# design.net
KiCad netlist of a schematic drawn in EasyEDA Pro
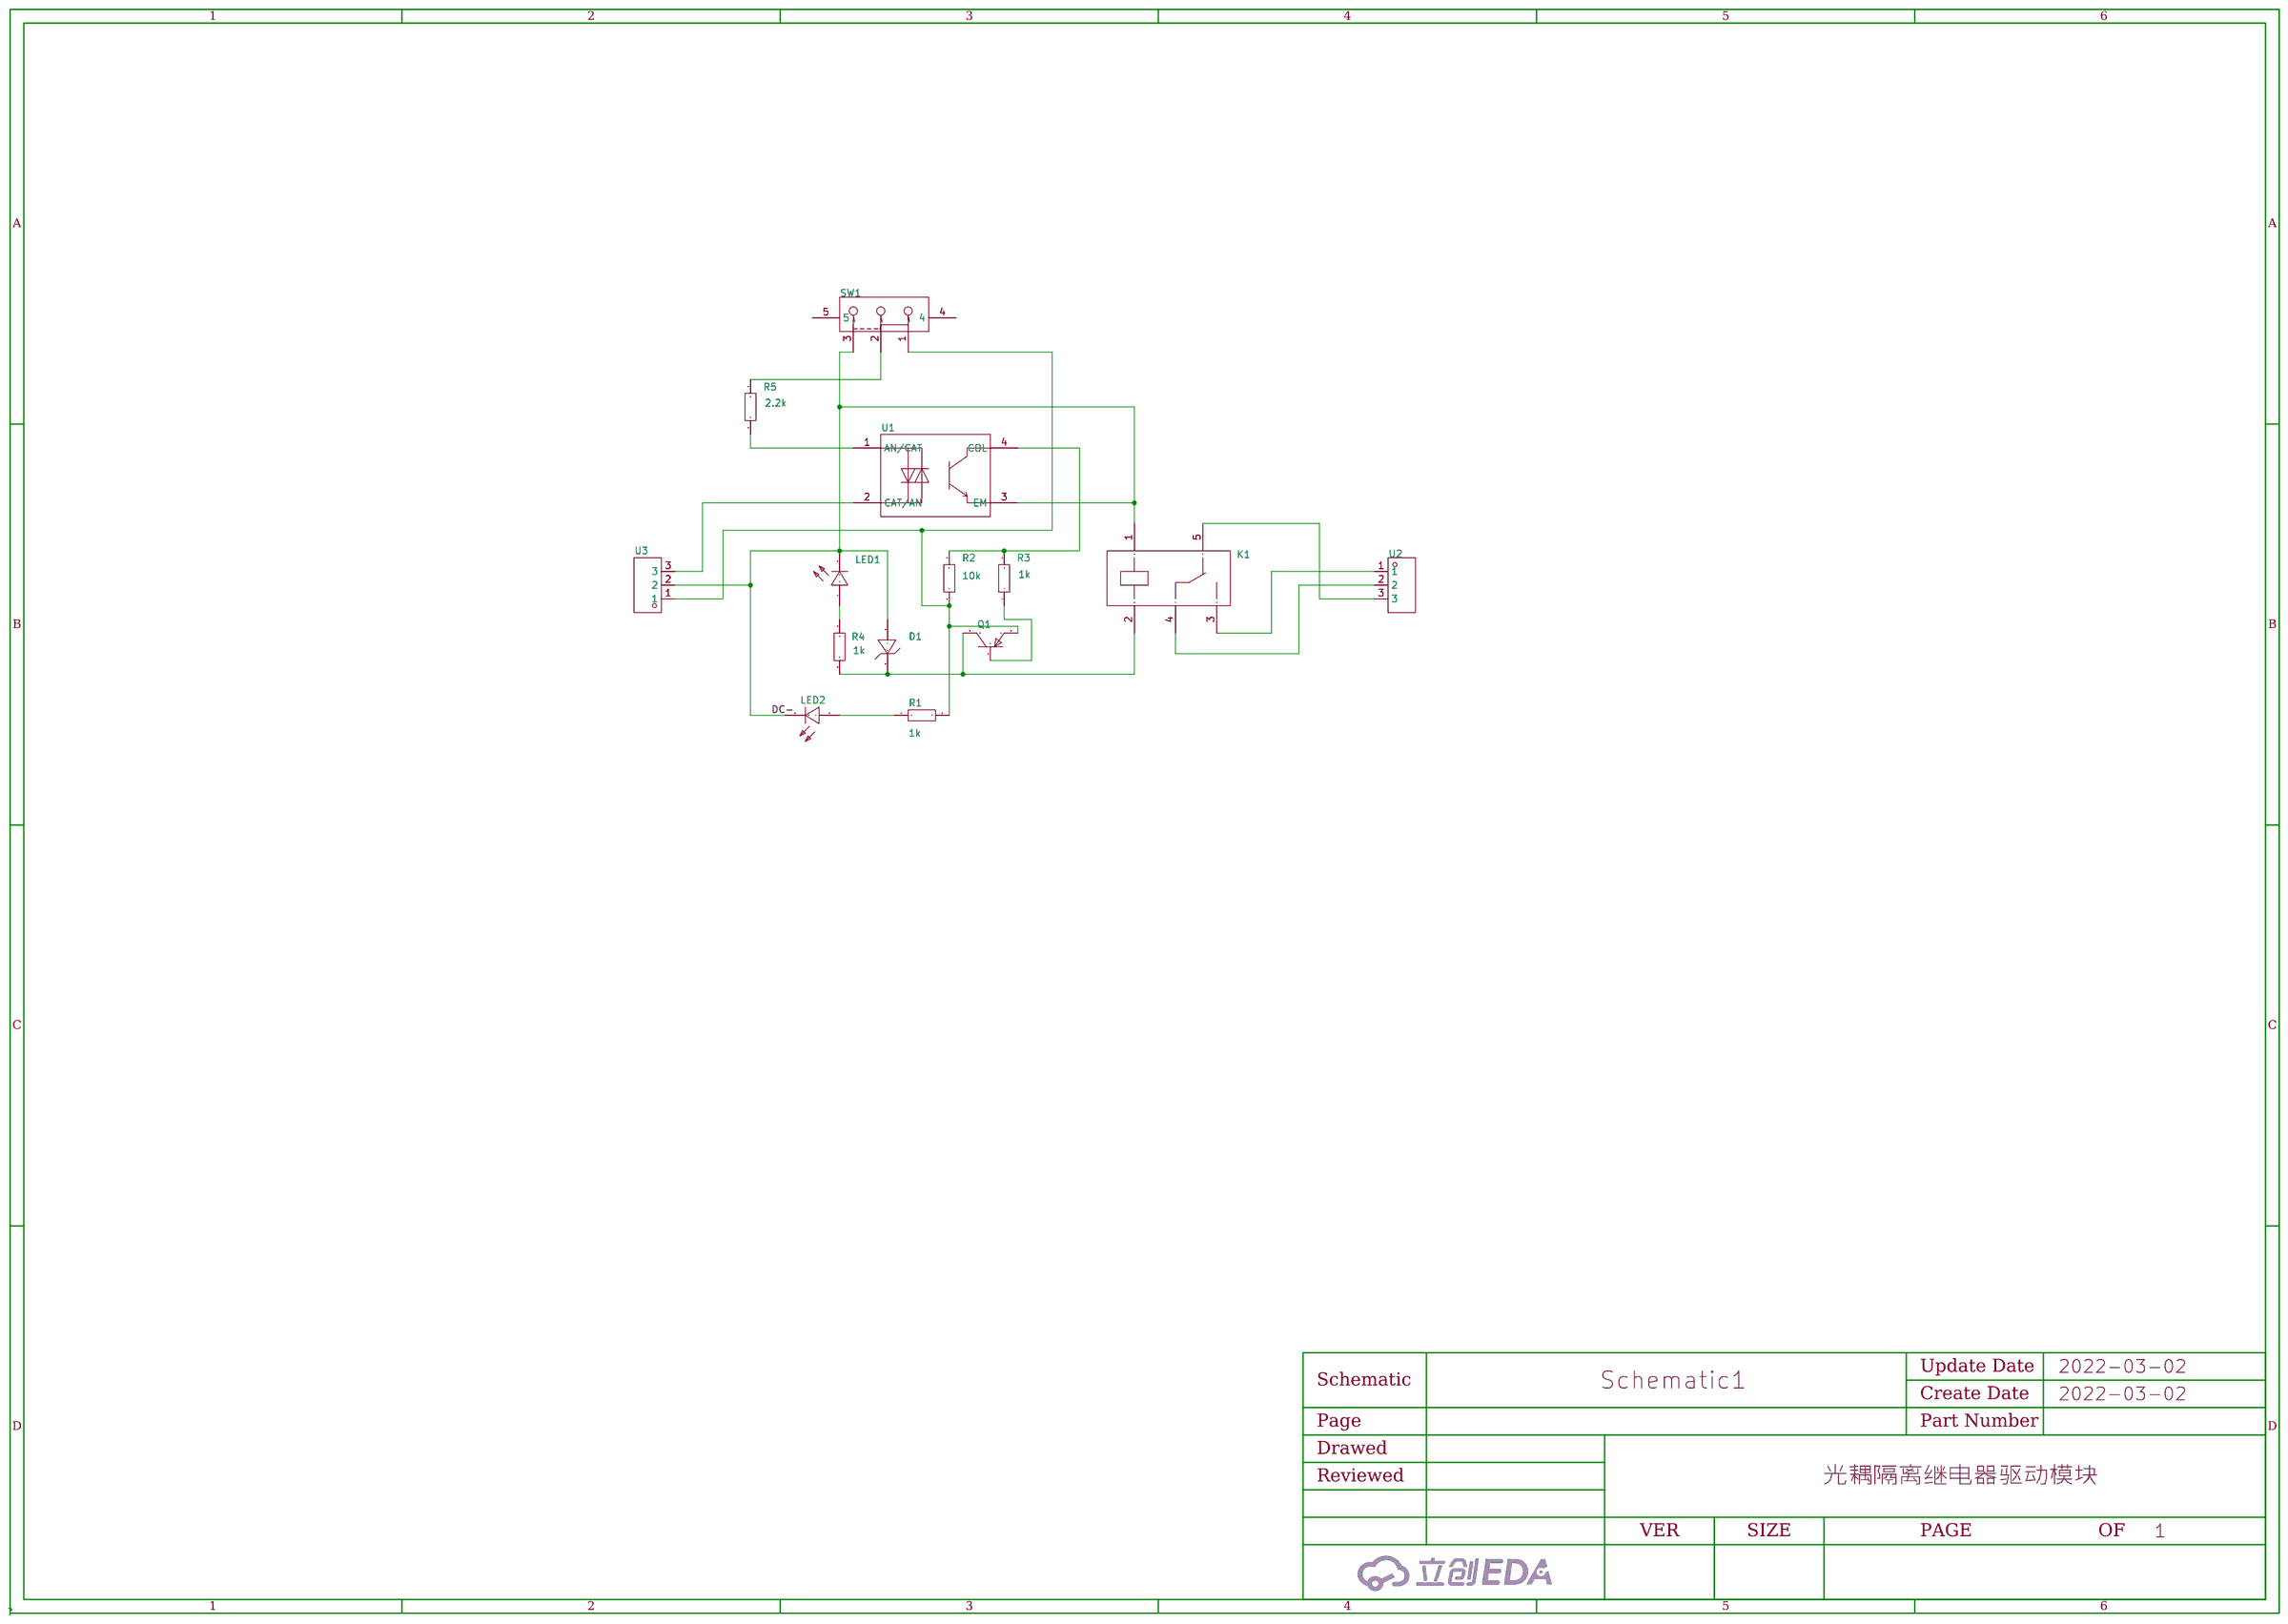
[diagram p0: schematic sheet]

(export (version "E")
  (design (tool "Eeschema 10.0.6"))
  (components
    (comp (ref "D1")
      (value "~")
      (footprint "easyedapro:LL-34_L3.5-W1.5-RD")
      (description "二极管配置:独立式;稳压值(标称值):-;稳压值(范围):4.94V~5.2V;精度:-;功率:500mW;反向电流(Ir):5A@1.5V;阻抗(Zzt):20;")
      (fields
        (field (name "Manufacturer Part") "GLZ5.1B_R1_10001")
        (field (name "Manufacturer") "PANJIT(强茂)")
      )
      (libsource (lib "easyedapro") (part "GLZ5.1B_R1_10001"))
    )
    (comp (ref "K1")
      (value "~")
      (footprint "easyedapro:RELAY-TH_HF3FF-XX-1ZXX-XXX")
      (description "继电器类型:General Purpose;线圈类型:Non Latching;线圈电压:5VDC;触点形式:SPDT;触点的额定电流:10A;")
      (fields
        (field (name "Manufacturer Part") "JQC-3FF/005-1ZS(551)")
        (field (name "Manufacturer") "HF(宏发)")
      )
      (libsource (lib "easyedapro") (part "JQC-3FF/05-1ZS(551)"))
    )
    (comp (ref "LED1")
      (value "~")
      (footprint "easyedapro:LED0603-R-RD")
      (fields
        (field (name "Manufacturer Part") "19-217/GHC-YR1S2/3T")
        (field (name "Manufacturer") "EVERLIGHT(台湾亿光)")
      )
      (libsource (lib "easyedapro") (part "19-217/GHC-YR1S2/3T"))
    )
    (comp (ref "LED2")
      (value "~")
      (footprint "easyedapro:LED0603-R-RD")
      (fields
        (field (name "Manufacturer Part") "19-217/GHC-YR1S2/3T")
        (field (name "Manufacturer") "EVERLIGHT(台湾亿光)")
      )
      (libsource (lib "easyedapro") (part "19-217/GHC-YR1S2/3T"))
    )
    (comp (ref "Q1")
      (value "~")
      (footprint "easyedapro:SOT-23-3_L2.9-W1.3-P1.90-LS2.4-BR")
      (description "晶体管类型:PNP;集射极击穿电压(Vceo):25V;集电极电流(Ic):500mA;功率(Pd):300mW;")
      (fields (field (name "Manufacturer Part") "S8550 2TY") (field (name "Manufacturer") "CJ（江苏长电/长晶）"))
      (libsource (lib "easyedapro") (part "S8550_C2147"))
    )
    (comp (ref "R1")
      (value "1k")
      (footprint "easyedapro:R0603")
      (description "电阻类型:薄膜电阻;阻值:10k;精度:±0.1%;功率:100mW;温度系数:±25ppm/;最大工作电压:75V;工作温度范围:-55~+155;")
      (fields
        (field (name "Manufacturer Part") "TR0603B10K0P0525Z")
        (field (name "Manufacturer") "EVER OHMS(天二科技)")
      )
      (libsource (lib "easyedapro") (part "TR0603B10KP05250.1W"))
    )
    (comp (ref "R2")
      (value "10k")
      (footprint "easyedapro:R0603")
      (description "电阻类型:薄膜电阻;阻值:10k;精度:±0.1%;功率:100mW;温度系数:±25ppm/;最大工作电压:75V;工作温度范围:-55~+155;")
      (fields
        (field (name "Manufacturer Part") "TR0603B10K0P0525Z")
        (field (name "Manufacturer") "EVER OHMS(天二科技)")
      )
      (libsource (lib "easyedapro") (part "TR0603B10KP05250.1W"))
    )
    (comp (ref "R3")
      (value "1k")
      (footprint "easyedapro:R0603")
      (description "电阻类型:薄膜电阻;阻值:10k;精度:±0.1%;功率:100mW;温度系数:±25ppm/;最大工作电压:75V;工作温度范围:-55~+155;")
      (fields
        (field (name "Manufacturer Part") "TR0603B10K0P0525Z")
        (field (name "Manufacturer") "EVER OHMS(天二科技)")
      )
      (libsource (lib "easyedapro") (part "TR0603B10KP05250.1W"))
    )
    (comp (ref "R4")
      (value "1k")
      (footprint "easyedapro:R0603")
      (description "电阻类型:薄膜电阻;阻值:10k;精度:±0.1%;功率:100mW;温度系数:±25ppm/;最大工作电压:75V;工作温度范围:-55~+155;")
      (fields
        (field (name "Manufacturer Part") "TR0603B10K0P0525Z")
        (field (name "Manufacturer") "EVER OHMS(天二科技)")
      )
      (libsource (lib "easyedapro") (part "TR0603B10KP05250.1W"))
    )
    (comp (ref "R5")
      (value "2.2k")
      (footprint "easyedapro:R0603")
      (description "电阻类型:薄膜电阻;阻值:10k;精度:±0.1%;功率:100mW;温度系数:±25ppm/;最大工作电压:75V;工作温度范围:-55~+155;")
      (fields
        (field (name "Manufacturer Part") "TR0603B10K0P0525Z")
        (field (name "Manufacturer") "EVER OHMS(天二科技)")
      )
      (libsource (lib "easyedapro") (part "TR0603B10KP05250.1W"))
    )
    (comp (ref "SW1")
      (value "~")
      (footprint "easyedapro:SW-TH_SK-12D02VG3")
      (fields (field (name "Manufacturer Part") "SK-12D02VG3") (field (name "Manufacturer") "SOFNG(硕方)"))
      (libsource (lib "easyedapro") (part "SK-12D02"))
    )
    (comp (ref "U1")
      (value "~")
      (footprint "easyedapro:SOP-4_L3.9-W4.4-P2.54-LS7.0-TL")
      (description "产品类型:晶体管输出;输入类型:AC, DC;通道数目:1;隔离电压:3750Vrms;")
      (fields (field (name "Manufacturer Part") "LTV-354T-A") (field (name "Manufacturer") "LITEON(台湾光宝)"))
      (libsource (lib "easyedapro") (part "LTV-354T-A"))
    )
    (comp (ref "U2")
      (value "~")
      (footprint "easyedapro:CONN-TH_3P-P5.00_KF301-5.0-3P")
      (description "间距:5mm;排数:1;每排PIN数:3;安装方式:直针;额定电流:17A;额定电压:250V;线规 - AWG:14~22;线规 - mm?:1.5;工作温度范围:-30~+120;颜色:蓝色;")
      (fields (field (name "Manufacturer Part") "KF301-5.0-3P") (field (name "Manufacturer") "KEFA(科发)"))
      (libsource (lib "easyedapro") (part "KF301-5.0-3P"))
    )
    (comp (ref "U3")
      (value "~")
      (footprint "easyedapro:CONN-TH_3P-P5.00_KF301-5.0-3P")
      (description "间距:5mm;排数:1;每排PIN数:3;安装方式:直针;额定电流:17A;额定电压:250V;线规 - AWG:14~22;线规 - mm?:1.5;工作温度范围:-30~+120;颜色:蓝色;")
      (fields (field (name "Manufacturer Part") "KF301-5.0-3P") (field (name "Manufacturer") "KEFA(科发)"))
      (libsource (lib "easyedapro") (part "KF301-5.0-3P"))
    )
  )
  (nets
    (net (code "1") (name "/DC-") (class "Default")
      (node (ref "D1") (pin "2") (pinfunction "A_2") (pintype "input"))
      (node (ref "K1") (pin "1") (pinfunction "1_1") (pintype "input"))
      (node (ref "LED1") (pin "2") (pinfunction "C_2") (pintype "input"))
      (node (ref "LED2") (pin "2") (pinfunction "C_2") (pintype "input"))
      (node (ref "SW1") (pin "3") (pinfunction "3_3") (pintype "input"))
      (node (ref "U1") (pin "3") (pinfunction "EM_3") (pintype "input"))
      (node (ref "U3") (pin "2") (pinfunction "2_2") (pintype "input"))
    )
    (net (code "2") (name "Net-(D1-C)") (class "Default")
      (node (ref "D1") (pin "1") (pinfunction "C_1") (pintype "input"))
      (node (ref "K1") (pin "2") (pinfunction "2_2") (pintype "input"))
      (node (ref "Q1") (pin "3") (pinfunction "C_3") (pintype "input"))
      (node (ref "R4") (pin "1") (pinfunction "1_1") (pintype "input"))
    )
    (net (code "3") (name "Net-(K1-Pad3)") (class "Default")
      (node (ref "K1") (pin "3") (pinfunction "3_3") (pintype "input"))
      (node (ref "U2") (pin "1") (pinfunction "1_1") (pintype "input"))
    )
    (net (code "4") (name "Net-(K1-Pad4)") (class "Default")
      (node (ref "K1") (pin "4") (pinfunction "4_4") (pintype "input"))
      (node (ref "U2") (pin "2") (pinfunction "2_2") (pintype "input"))
    )
    (net (code "5") (name "Net-(K1-Pad5)") (class "Default")
      (node (ref "K1") (pin "5") (pinfunction "5_5") (pintype "input"))
      (node (ref "U2") (pin "3") (pinfunction "3_3") (pintype "input"))
    )
    (net (code "6") (name "Net-(LED1-A)") (class "Default")
      (node (ref "LED1") (pin "1") (pinfunction "A_1") (pintype "input"))
      (node (ref "R4") (pin "2") (pinfunction "2_2") (pintype "input"))
    )
    (net (code "7") (name "Net-(LED2-A)") (class "Default")
      (node (ref "LED2") (pin "1") (pinfunction "A_1") (pintype "input"))
      (node (ref "R1") (pin "1") (pinfunction "1_1") (pintype "input"))
    )
    (net (code "8") (name "Net-(Q1-B)") (class "Default")
      (node (ref "Q1") (pin "1") (pinfunction "B_1") (pintype "input"))
      (node (ref "R3") (pin "1") (pinfunction "1_1") (pintype "input"))
    )
    (net (code "9") (name "Net-(Q1-E)") (class "Default")
      (node (ref "Q1") (pin "2") (pinfunction "E_2") (pintype "input"))
      (node (ref "R1") (pin "2") (pinfunction "2_2") (pintype "input"))
      (node (ref "R2") (pin "1") (pinfunction "1_1") (pintype "input"))
      (node (ref "SW1") (pin "1") (pinfunction "1_1") (pintype "input"))
      (node (ref "U3") (pin "1") (pinfunction "1_1") (pintype "input"))
    )
    (net (code "10") (name "Net-(R5-Pad2)") (class "Default")
      (node (ref "R5") (pin "2") (pinfunction "2_2") (pintype "input"))
      (node (ref "SW1") (pin "2") (pinfunction "2_2") (pintype "input"))
    )
    (net (code "11") (name "Net-(U1-AN{slash}CAT)") (class "Default")
      (node (ref "R5") (pin "1") (pinfunction "1_1") (pintype "input"))
      (node (ref "U1") (pin "1") (pinfunction "AN/CAT_1") (pintype "input"))
    )
    (net (code "12") (name "Net-(U1-CAT{slash}AN)") (class "Default")
      (node (ref "U1") (pin "2") (pinfunction "CAT/AN_2") (pintype "input"))
      (node (ref "U3") (pin "3") (pinfunction "3_3") (pintype "input"))
    )
    (net (code "13") (name "Net-(U1-COL)") (class "Default")
      (node (ref "R2") (pin "2") (pinfunction "2_2") (pintype "input"))
      (node (ref "R3") (pin "2") (pinfunction "2_2") (pintype "input"))
      (node (ref "U1") (pin "4") (pinfunction "COL_4") (pintype "input"))
    )
    (net (code "14") (name "unconnected-(SW1-Pad4)") (class "Default")
      (node (ref "SW1") (pin "4") (pinfunction "4_4") (pintype "input"))
    )
    (net (code "15") (name "unconnected-(SW1-Pad5)") (class "Default")
      (node (ref "SW1") (pin "5") (pinfunction "5_5") (pintype "input"))
    )
  )
)
